# ProPrj_Crowd_Guarddd_2026-06-03.net
KiCad netlist of a schematic drawn in EasyEDA Pro
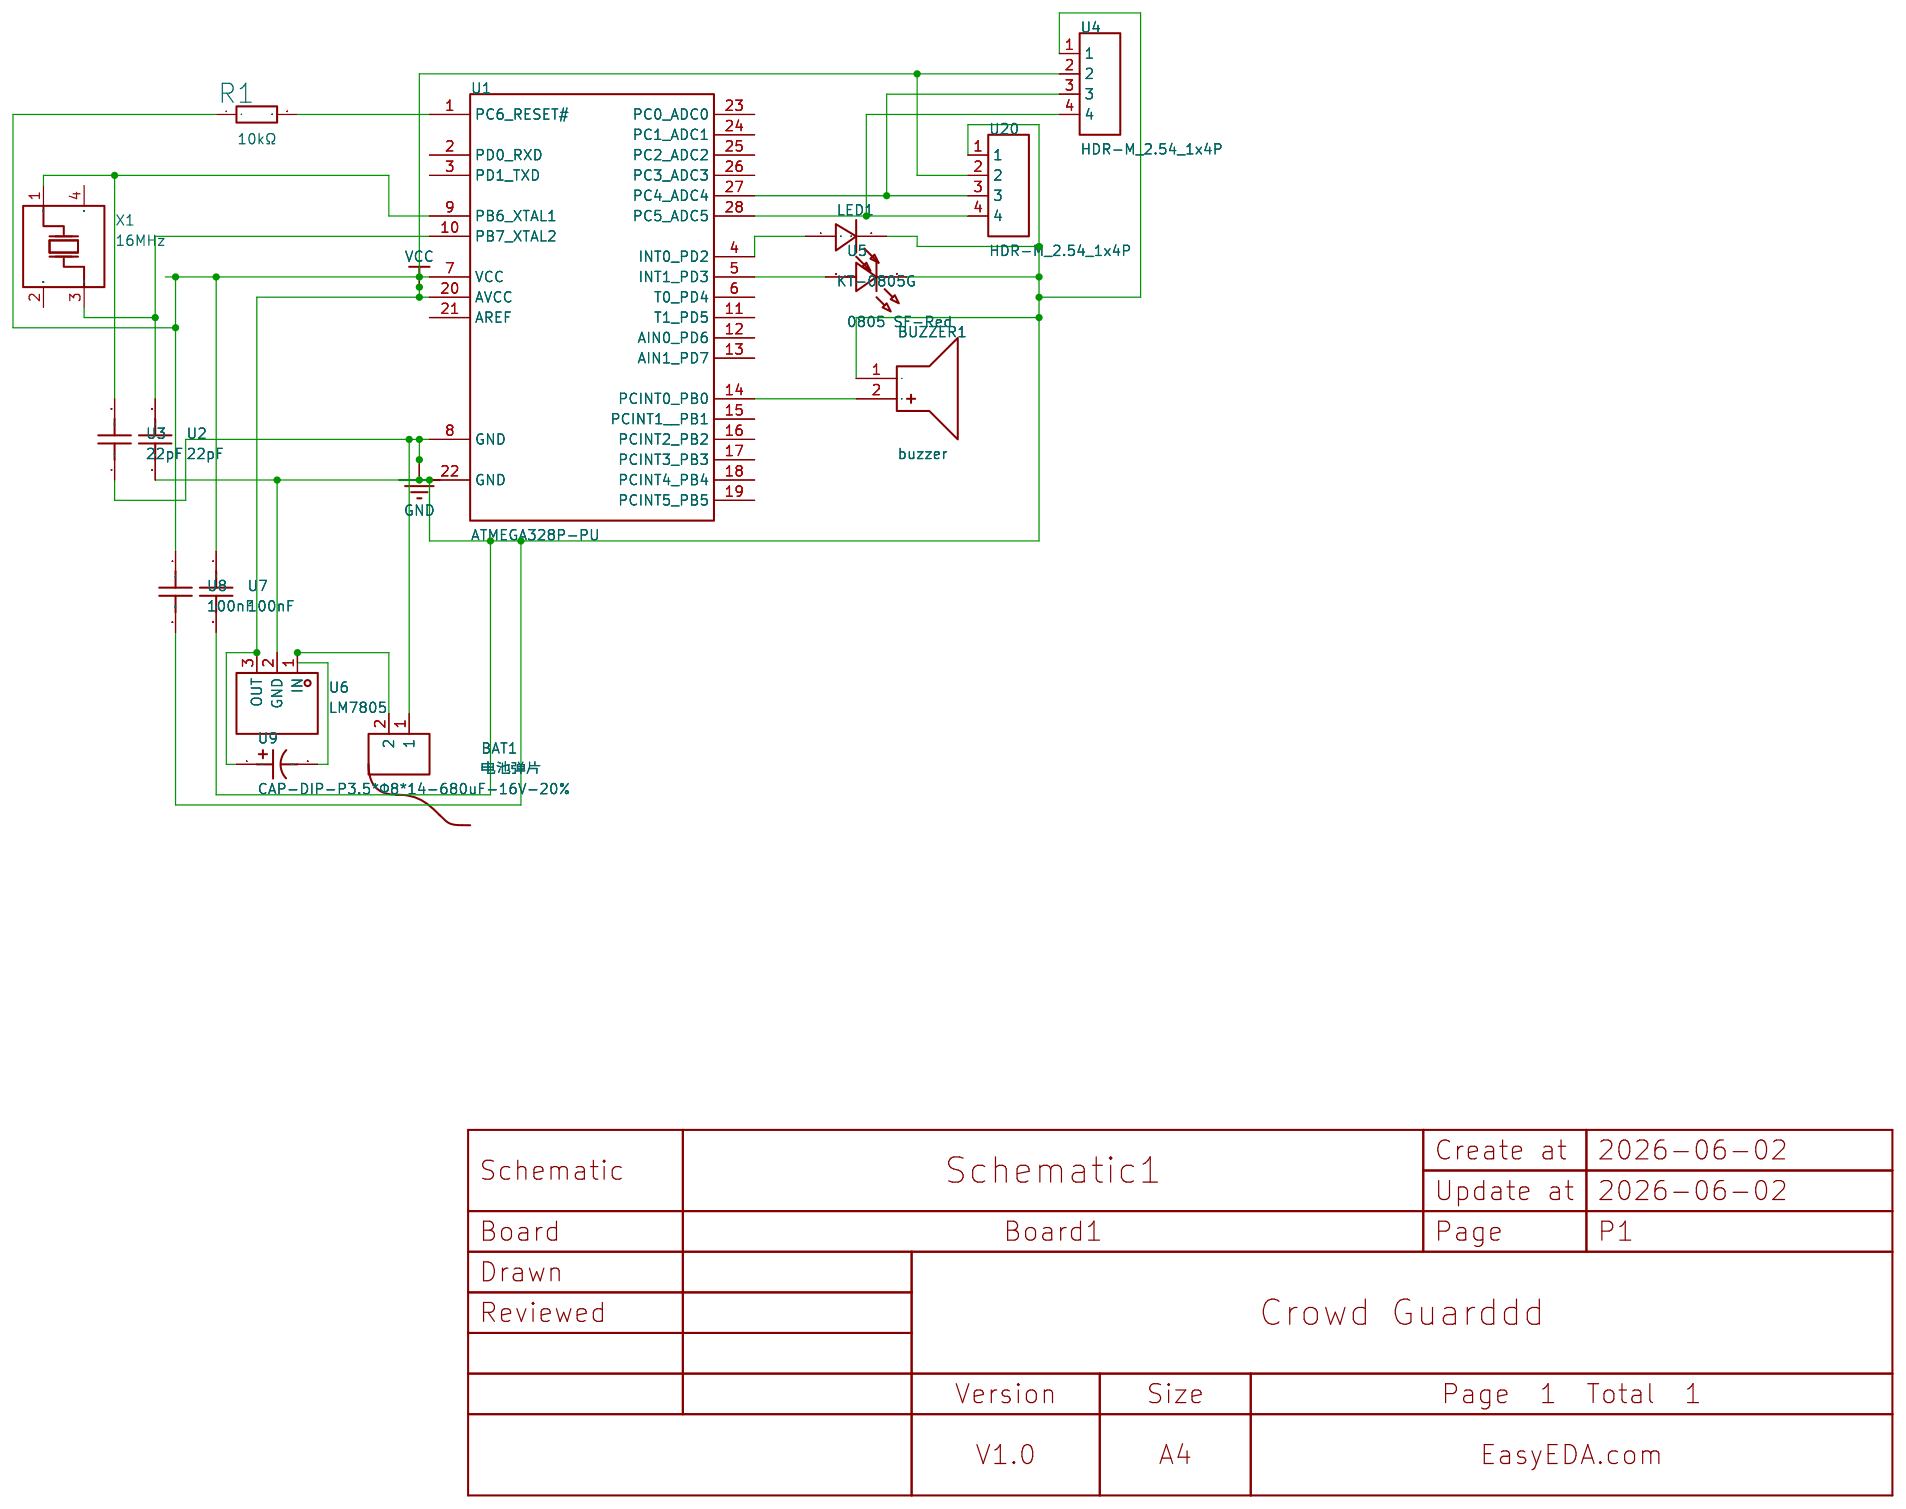
[diagram p0: schematic sheet]

(export (version "E")
  (design (tool "Eeschema 10.0.6"))
  (components
    (comp (ref "BAT1")
      (value "电池弹片")
      (footprint "easyedapro:BAT-TH_L4.0-W3.0-P3.7")
      (libsource (lib "easyedapro") (part "电池弹片_C9900020299"))
    )
    (comp (ref "BUZZER1")
      (value "buzzer")
      (footprint "easyedapro:BUZ-TH_BD12.0-P6.00-D0.9-RD")
      (libsource (lib "easyedapro") (part "BUZZER"))
    )
    (comp (ref "LED1")
      (value "KT-0805G")
      (footprint "easyedapro:LED0805-R-RD")
      (fields (field (name "Manufacturer") "KENTO"))
      (libsource (lib "easyedapro") (part "0805G (Green)"))
    )
    (comp (ref "R1")
      (value "10kΩ")
      (footprint "easyedapro:R0603")
      (fields
        (field (name "Manufacturer Part") "0603WAF1002T5E")
        (field (name "Manufacturer") "UNI-ROYAL(厚声)")
      )
      (libsource (lib "easyedapro") (part "0603WAF1002T5E"))
    )
    (comp (ref "U1")
      (value "ATMEGA328P-PU")
      (footprint "easyedapro:DIP-28_L34.6-W7.3-P2.54-LS10.2-BL")
      (fields (field (name "Manufacturer") "MICROCHIP(美国微芯)"))
      (libsource (lib "easyedapro") (part "ATMEGA328P-PU"))
    )
    (comp (ref "U2")
      (value "22pF")
      (footprint "easyedapro:C0805")
      (fields (field (name "Manufacturer Part") "C0805C220J1GACTU") (field (name "Manufacturer") "KEMET(基美)"))
      (libsource (lib "easyedapro") (part "C0805C220J1GACTU"))
    )
    (comp (ref "U3")
      (value "22pF")
      (footprint "easyedapro:C0805")
      (fields (field (name "Manufacturer Part") "C0805C220J1GACTU") (field (name "Manufacturer") "KEMET(基美)"))
      (libsource (lib "easyedapro") (part "C0805C220J1GACTU"))
    )
    (comp (ref "U4")
      (value "HDR-M_2.54_1x4P")
      (footprint "easyedapro:HDR-TH_HDR-M_2.54_1X4P")
      (libsource (lib "easyedapro") (part "HDR-M_2.54_1X4P"))
    )
    (comp (ref "U5")
      (value "0805 SF-Red")
      (footprint "easyedapro:LED0805-RD_RED")
      (libsource (lib "easyedapro") (part "0805 SF-RED"))
    )
    (comp (ref "U6")
      (value "LM7805")
      (footprint "easyedapro:TO-220-3_L10.0-W4.5-P2.54-L")
      (fields (field (name "Manufacturer") "TF(拓锋)"))
      (libsource (lib "easyedapro") (part "LM7805"))
    )
    (comp (ref "U7")
      (value "100nF")
      (footprint "easyedapro:CAP-TH_L5.0-W2.5-P5.00-D1.0")
      (libsource (lib "easyedapro") (part "100NF_C9900015256"))
    )
    (comp (ref "U8")
      (value "100nF")
      (footprint "easyedapro:CAP-TH_L5.0-W2.5-P5.00-D1.0")
      (libsource (lib "easyedapro") (part "100NF_C9900015256"))
    )
    (comp (ref "U9")
      (value "CAP-DIP-P3.5*Φ8*14-680uF-16V-20%")
      (footprint "easyedapro:CAP-TH_BD8.0-P3.50-D0.5-FD")
      (libsource (lib "easyedapro") (part "CAP-DIP-P3.5*Φ8*14-680UF-16V-20%"))
    )
    (comp (ref "U20")
      (value "HDR-M_2.54_1x4P")
      (footprint "easyedapro:HDR-TH_HDR-M_2.54_1X4P")
      (libsource (lib "easyedapro") (part "HDR-M_2.54_1X4P"))
    )
    (comp (ref "X1")
      (value "16MHz")
      (footprint "easyedapro:CRYSTAL-SMD_4P-L3.2-W2.5-BL")
      (fields (field (name "Manufacturer Part") "X322516MLB4SI") (field (name "Manufacturer") "YXC(扬兴晶振)"))
      (libsource (lib "easyedapro") (part "X322516MLB4SI"))
    )
  )
  (nets
    (net (code "1") (name "GND") (class "Default")
      (node (ref "BAT1") (pin "1") (pinfunction "1_1") (pintype "unspecified"))
      (node (ref "BUZZER1") (pin "1") (pinfunction "-_1") (pintype "unspecified"))
      (node (ref "LED1") (pin "2") (pinfunction "K_2") (pintype "unspecified"))
      (node (ref "U1") (pin "22") (pinfunction "GND_22") (pintype "unspecified"))
      (node (ref "U1") (pin "8") (pinfunction "GND_8") (pintype "unspecified"))
      (node (ref "U2") (pin "1") (pinfunction "1_1") (pintype "unspecified"))
      (node (ref "U20") (pin "1") (pinfunction "1_1") (pintype "unspecified"))
      (node (ref "U3") (pin "1") (pinfunction "1_1") (pintype "unspecified"))
      (node (ref "U4") (pin "1") (pinfunction "1_1") (pintype "unspecified"))
      (node (ref "U5") (pin "1") (pinfunction "K_1") (pintype "unspecified"))
      (node (ref "U6") (pin "2") (pinfunction "GND_2") (pintype "input"))
      (node (ref "U7") (pin "2") (pinfunction "2_2") (pintype "unspecified"))
      (node (ref "U8") (pin "2") (pinfunction "2_2") (pintype "unspecified"))
    )
    (net (code "2") (name "Net-(BUZZER1-+)") (class "Default")
      (node (ref "BUZZER1") (pin "2") (pinfunction "+_2") (pintype "unspecified"))
      (node (ref "U1") (pin "14") (pinfunction "PCINT0_PB0_14") (pintype "bidirectional"))
    )
    (net (code "3") (name "Net-(LED1-A)") (class "Default")
      (node (ref "LED1") (pin "1") (pinfunction "A_1") (pintype "unspecified"))
      (node (ref "U1") (pin "4") (pinfunction "INT0_PD2_4") (pintype "bidirectional"))
    )
    (net (code "4") (name "Net-(U1-INT1_PD3)") (class "Default")
      (node (ref "U1") (pin "5") (pinfunction "INT1_PD3_5") (pintype "bidirectional"))
      (node (ref "U5") (pin "2") (pinfunction "A_2") (pintype "unspecified"))
    )
    (net (code "5") (name "Net-(U1-PB6_XTAL1)") (class "Default")
      (node (ref "U1") (pin "9") (pinfunction "PB6_XTAL1_9") (pintype "bidirectional"))
      (node (ref "U3") (pin "2") (pinfunction "2_2") (pintype "unspecified"))
      (node (ref "X1") (pin "1") (pinfunction "OSC1_1") (pintype "unspecified"))
    )
    (net (code "6") (name "Net-(U1-PB7_XTAL2)") (class "Default")
      (node (ref "U1") (pin "10") (pinfunction "PB7_XTAL2_10") (pintype "bidirectional"))
      (node (ref "U2") (pin "2") (pinfunction "2_2") (pintype "unspecified"))
      (node (ref "X1") (pin "3") (pinfunction "OSC2_3") (pintype "unspecified"))
    )
    (net (code "7") (name "Net-(U1-PC4_ADC4)") (class "Default")
      (node (ref "U1") (pin "27") (pinfunction "PC4_ADC4_27") (pintype "bidirectional"))
      (node (ref "U20") (pin "3") (pinfunction "3_3") (pintype "unspecified"))
      (node (ref "U4") (pin "3") (pinfunction "3_3") (pintype "unspecified"))
    )
    (net (code "8") (name "Net-(U1-PC5_ADC5)") (class "Default")
      (node (ref "U1") (pin "28") (pinfunction "PC5_ADC5_28") (pintype "bidirectional"))
      (node (ref "U20") (pin "4") (pinfunction "4_4") (pintype "unspecified"))
      (node (ref "U4") (pin "4") (pinfunction "4_4") (pintype "unspecified"))
    )
    (net (code "9") (name "Net-(U1-PC6_RESET#)") (class "Default")
      (node (ref "R1") (pin "2") (pinfunction "2_2") (pintype "input"))
      (node (ref "U1") (pin "1") (pinfunction "PC6_RESET#_1") (pintype "bidirectional"))
    )
    (net (code "10") (name "Net-(U6-IN)") (class "Default")
      (node (ref "BAT1") (pin "2") (pinfunction "2_2") (pintype "unspecified"))
      (node (ref "U6") (pin "1") (pinfunction "IN_1") (pintype "input"))
      (node (ref "U9") (pin "2") (pinfunction "2_2") (pintype "input"))
    )
    (net (code "11") (name "VCC") (class "Default")
      (node (ref "R1") (pin "1") (pinfunction "1_1") (pintype "input"))
      (node (ref "U1") (pin "20") (pinfunction "AVCC_20") (pintype "unspecified"))
      (node (ref "U1") (pin "7") (pinfunction "VCC_7") (pintype "unspecified"))
      (node (ref "U20") (pin "2") (pinfunction "2_2") (pintype "unspecified"))
      (node (ref "U4") (pin "2") (pinfunction "2_2") (pintype "unspecified"))
      (node (ref "U6") (pin "3") (pinfunction "OUT_3") (pintype "input"))
      (node (ref "U7") (pin "1") (pinfunction "1_1") (pintype "unspecified"))
      (node (ref "U8") (pin "1") (pinfunction "1_1") (pintype "unspecified"))
      (node (ref "U9") (pin "1") (pinfunction "1_1") (pintype "input"))
    )
    (net (code "12") (name "unconnected-(U1-AIN0_PD6-Pad12)") (class "Default")
      (node (ref "U1") (pin "12") (pinfunction "AIN0_PD6_12") (pintype "bidirectional"))
    )
    (net (code "13") (name "unconnected-(U1-AIN1_PD7-Pad13)") (class "Default")
      (node (ref "U1") (pin "13") (pinfunction "AIN1_PD7_13") (pintype "bidirectional"))
    )
    (net (code "14") (name "unconnected-(U1-AREF-Pad21)") (class "Default")
      (node (ref "U1") (pin "21") (pinfunction "AREF_21") (pintype "unspecified"))
    )
    (net (code "15") (name "unconnected-(U1-PC0_ADC0-Pad23)") (class "Default")
      (node (ref "U1") (pin "23") (pinfunction "PC0_ADC0_23") (pintype "bidirectional"))
    )
    (net (code "16") (name "unconnected-(U1-PC1_ADC1-Pad24)") (class "Default")
      (node (ref "U1") (pin "24") (pinfunction "PC1_ADC1_24") (pintype "bidirectional"))
    )
    (net (code "17") (name "unconnected-(U1-PC2_ADC2-Pad25)") (class "Default")
      (node (ref "U1") (pin "25") (pinfunction "PC2_ADC2_25") (pintype "bidirectional"))
    )
    (net (code "18") (name "unconnected-(U1-PC3_ADC3-Pad26)") (class "Default")
      (node (ref "U1") (pin "26") (pinfunction "PC3_ADC3_26") (pintype "bidirectional"))
    )
    (net (code "19") (name "unconnected-(U1-PCINT1__PB1-Pad15)") (class "Default")
      (node (ref "U1") (pin "15") (pinfunction "PCINT1__PB1_15") (pintype "bidirectional"))
    )
    (net (code "20") (name "unconnected-(U1-PCINT2_PB2-Pad16)") (class "Default")
      (node (ref "U1") (pin "16") (pinfunction "PCINT2_PB2_16") (pintype "bidirectional"))
    )
    (net (code "21") (name "unconnected-(U1-PCINT3_PB3-Pad17)") (class "Default")
      (node (ref "U1") (pin "17") (pinfunction "PCINT3_PB3_17") (pintype "bidirectional"))
    )
    (net (code "22") (name "unconnected-(U1-PCINT4_PB4-Pad18)") (class "Default")
      (node (ref "U1") (pin "18") (pinfunction "PCINT4_PB4_18") (pintype "bidirectional"))
    )
    (net (code "23") (name "unconnected-(U1-PCINT5_PB5-Pad19)") (class "Default")
      (node (ref "U1") (pin "19") (pinfunction "PCINT5_PB5_19") (pintype "bidirectional"))
    )
    (net (code "24") (name "unconnected-(U1-PD0_RXD-Pad2)") (class "Default")
      (node (ref "U1") (pin "2") (pinfunction "PD0_RXD_2") (pintype "bidirectional"))
    )
    (net (code "25") (name "unconnected-(U1-PD1_TXD-Pad3)") (class "Default")
      (node (ref "U1") (pin "3") (pinfunction "PD1_TXD_3") (pintype "bidirectional"))
    )
    (net (code "26") (name "unconnected-(U1-T0_PD4-Pad6)") (class "Default")
      (node (ref "U1") (pin "6") (pinfunction "T0_PD4_6") (pintype "bidirectional"))
    )
    (net (code "27") (name "unconnected-(U1-T1_PD5-Pad11)") (class "Default")
      (node (ref "U1") (pin "11") (pinfunction "T1_PD5_11") (pintype "bidirectional"))
    )
    (net (code "28") (name "unconnected-(X1-GND-Pad2)") (class "Default")
      (node (ref "X1") (pin "2") (pinfunction "GND_2") (pintype "unspecified"))
    )
    (net (code "29") (name "unconnected-(X1-GND-Pad4)") (class "Default")
      (node (ref "X1") (pin "4") (pinfunction "GND_4") (pintype "unspecified"))
    )
  )
)
